# TankBoardSheet4.net
KiCad netlist of a schematic drawn in Altium Designer
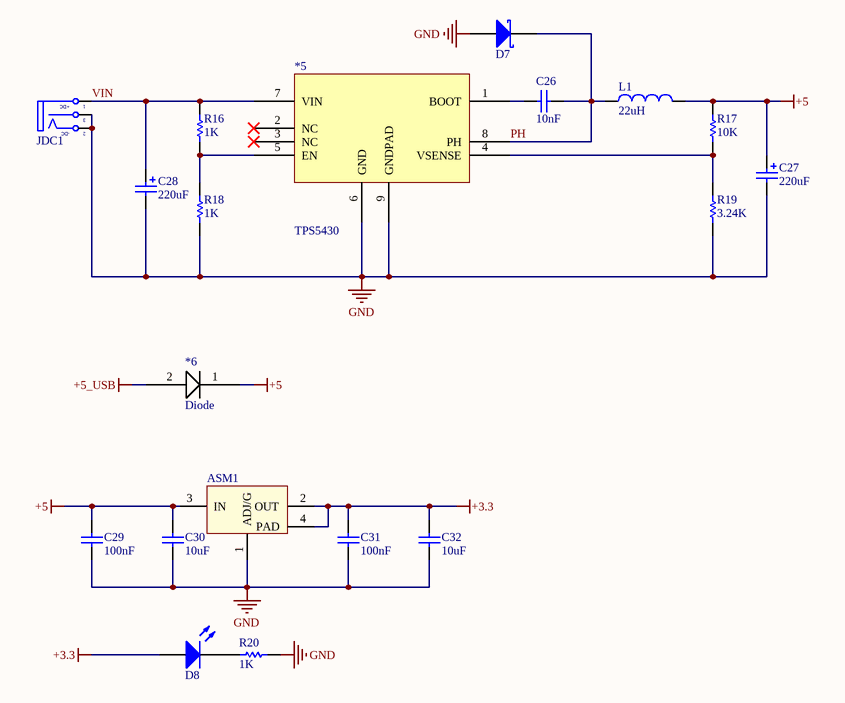
[diagram p0: TankBoardSheet4.SchDoc]

(export (version "E")
  (design (tool "Eeschema 10.0.6"))
  (components
    (comp (ref "*5")
      (value "TPS5430")
      (footprint "SOIC127P600X170_HS-9N")
      (libsource (lib "MiclsLib") (part "TPS5430"))
    )
    (comp (ref "*6")
      (value "Diode")
      (footprint "DIODE SMA (DO-214AC)")
      (libsource (lib "MiclsLib") (part "Diode"))
    )
    (comp (ref "ASM1")
      (value "LM1117")
      (footprint "SOT223-4N")
      (description "Available in 1.8V, 2.5V, 2.85V, 3.3V, 5V, and  Adjustable Versions")
      (libsource (lib "PIF_Library") (part "LM1117"))
    )
    (comp (ref "C26")
      (value "10nF")
      (footprint "CAP-SM-0603")
      (description "Capacitor")
      (fields (field (name "Comment") "Cap Non-Pol SMD"))
      (libsource (lib "PIF_Library") (part "Cap Non-Pol SMD"))
    )
    (comp (ref "C27")
      (value "220uF")
      (footprint "CAP ALU SIZE D")
      (description "Polarized Capacitor (Radial)")
      (fields (field (name "Comment") "Cap Pol SMD"))
      (libsource (lib "PIF_Library") (part "Cap Pol SMD"))
    )
    (comp (ref "C28")
      (value "220uF")
      (footprint "CAP ALU SIZE D")
      (description "Polarized Capacitor (Radial)")
      (fields (field (name "Comment") "Cap Pol SMD"))
      (libsource (lib "PIF_Library") (part "Cap Pol SMD"))
    )
    (comp (ref "C29")
      (value "100nF")
      (footprint "CAP-SM-0603")
      (description "Capacitor")
      (fields (field (name "Comment") "Cap Non-Pol SMD"))
      (libsource (lib "PIF_Library") (part "Cap Non-Pol SMD"))
    )
    (comp (ref "C30")
      (value "10uF")
      (footprint "CAP-SM-0603")
      (description "Capacitor")
      (fields (field (name "Comment") "Cap Non-Pol SMD"))
      (libsource (lib "PIF_Library") (part "Cap Non-Pol SMD"))
    )
    (comp (ref "C31")
      (value "100nF")
      (footprint "CAP-SM-0603")
      (description "Capacitor")
      (fields (field (name "Comment") "Cap Non-Pol SMD"))
      (libsource (lib "PIF_Library") (part "Cap Non-Pol SMD"))
    )
    (comp (ref "C32")
      (value "10uF")
      (footprint "CAP-SM-0603")
      (description "Capacitor")
      (fields (field (name "Comment") "Cap Non-Pol SMD"))
      (libsource (lib "PIF_Library") (part "Cap Non-Pol SMD"))
    )
    (comp (ref "D7")
      (value "D Schottky")
      (footprint "SS34")
      (description "Schottky Diode")
      (fields (field (name "PUBLISHER") "Altium Limited"))
      (libsource (lib "PIF_Library") (part "D Schottky"))
    )
    (comp (ref "D8")
      (value "LED SMD")
      (footprint "LED_0603_Blue")
      (description "LED")
      (libsource (lib "PIF_Library") (part "LED SMD"))
    )
    (comp (ref "JDC1")
      (value "Jack DC")
      (footprint "DC-IN")
      (description "Jack DC input")
      (libsource (lib "PIF_Library") (part "Jack DC"))
    )
    (comp (ref "L1")
      (value "22uH")
      (footprint "INDUCTOR 12.5x12.5")
      (description "Inductor")
      (libsource (lib "PIF_Library") (part "Inductor"))
    )
    (comp (ref "R16")
      (value "1K")
      (footprint "RES-SM-0603")
      (description "Resistor")
      (fields (field (name "Comment") "RESISTOR SMD"))
      (libsource (lib "PIF_Library") (part "RESISTOR SMD"))
    )
    (comp (ref "R17")
      (value "10K")
      (footprint "RES-SM-0603")
      (description "Resistor")
      (fields (field (name "Comment") "RESISTOR SMD"))
      (libsource (lib "PIF_Library") (part "RESISTOR SMD"))
    )
    (comp (ref "R18")
      (value "1K")
      (footprint "RES-SM-0603")
      (description "Resistor")
      (fields (field (name "Comment") "RESISTOR SMD"))
      (libsource (lib "PIF_Library") (part "RESISTOR SMD"))
    )
    (comp (ref "R19")
      (value "3.24K")
      (footprint "RES-SM-0603")
      (description "Resistor")
      (fields (field (name "Comment") "RESISTOR SMD"))
      (libsource (lib "PIF_Library") (part "RESISTOR SMD"))
    )
    (comp (ref "R20")
      (value "1K")
      (footprint "RES-SM-0603")
      (description "Resistor")
      (fields (field (name "Comment") "RESISTOR SMD"))
      (libsource (lib "PIF_Library") (part "RESISTOR SMD"))
    )
  )
  (nets
    (net (code "1") (name "+3.3") (class "Default")
      (node (ref "ASM1") (pin "2") (pinfunction "OUT_2") (pintype "passive"))
      (node (ref "ASM1") (pin "4") (pinfunction "PAD_4") (pintype "passive"))
      (node (ref "C31") (pin "1") (pinfunction "1_1") (pintype "passive"))
      (node (ref "C32") (pin "1") (pinfunction "1_1") (pintype "passive"))
      (node (ref "D8") (pin "1") (pinfunction "A_1") (pintype "passive"))
    )
    (net (code "2") (name "+5") (class "Default")
      (node (ref "*6") (pin "1") (pinfunction "3_1") (pintype "passive"))
      (node (ref "ASM1") (pin "3") (pinfunction "IN_3") (pintype "passive"))
      (node (ref "C27") (pin "1") (pinfunction "1_1") (pintype "passive"))
      (node (ref "C29") (pin "1") (pinfunction "1_1") (pintype "passive"))
      (node (ref "C30") (pin "1") (pinfunction "1_1") (pintype "passive"))
      (node (ref "L1") (pin "2") (pinfunction "2_2") (pintype "passive"))
      (node (ref "R17") (pin "2") (pinfunction "2_2") (pintype "passive"))
    )
    (net (code "3") (name "+5_USB") (class "Default")
      (node (ref "*6") (pin "2") (pinfunction "4_2") (pintype "passive"))
    )
    (net (code "4") (name "/PH") (class "Default")
      (node (ref "*5") (pin "8") (pinfunction "PH_8") (pintype "passive"))
      (node (ref "C26") (pin "1") (pinfunction "1_1") (pintype "passive"))
      (node (ref "D7") (pin "2") (pinfunction "K_2") (pintype "passive"))
      (node (ref "L1") (pin "1") (pinfunction "1_1") (pintype "passive"))
    )
    (net (code "5") (name "/VIN") (class "Default")
      (node (ref "*5") (pin "7") (pinfunction "VIN_7") (pintype "passive"))
      (node (ref "C28") (pin "1") (pinfunction "1_1") (pintype "passive"))
      (node (ref "JDC1") (pin "1") (pinfunction "T_1") (pintype "passive"))
      (node (ref "R16") (pin "2") (pinfunction "2_2") (pintype "passive"))
    )
    (net (code "6") (name "GND") (class "Default")
      (node (ref "*5") (pin "6") (pinfunction "GND_6") (pintype "passive"))
      (node (ref "*5") (pin "9") (pinfunction "GNDPAD_9") (pintype "passive"))
      (node (ref "ASM1") (pin "1") (pinfunction "ADJ/G_1") (pintype "passive"))
      (node (ref "C27") (pin "2") (pinfunction "2_2") (pintype "passive"))
      (node (ref "C28") (pin "2") (pinfunction "2_2") (pintype "passive"))
      (node (ref "C29") (pin "2") (pinfunction "2_2") (pintype "passive"))
      (node (ref "C30") (pin "2") (pinfunction "2_2") (pintype "passive"))
      (node (ref "C31") (pin "2") (pinfunction "2_2") (pintype "passive"))
      (node (ref "C32") (pin "2") (pinfunction "2_2") (pintype "passive"))
      (node (ref "D7") (pin "1") (pinfunction "A_1") (pintype "passive"))
      (node (ref "JDC1") (pin "2") (pinfunction "TN_2") (pintype "passive"))
      (node (ref "JDC1") (pin "3") (pinfunction "S_3") (pintype "power_in"))
      (node (ref "R18") (pin "1") (pinfunction "1_1") (pintype "passive"))
      (node (ref "R19") (pin "1") (pinfunction "1_1") (pintype "passive"))
      (node (ref "R20") (pin "1") (pinfunction "1_1") (pintype "passive"))
    )
    (net (code "7") (name "Net-(*5-BOOT)") (class "Default")
      (node (ref "*5") (pin "1") (pinfunction "BOOT_1") (pintype "passive"))
      (node (ref "C26") (pin "2") (pinfunction "2_2") (pintype "passive"))
    )
    (net (code "8") (name "Net-(*5-EN)") (class "Default")
      (node (ref "*5") (pin "5") (pinfunction "EN_5") (pintype "passive"))
      (node (ref "R16") (pin "1") (pinfunction "1_1") (pintype "passive"))
      (node (ref "R18") (pin "2") (pinfunction "2_2") (pintype "passive"))
    )
    (net (code "9") (name "Net-(*5-VSENSE)") (class "Default")
      (node (ref "*5") (pin "4") (pinfunction "VSENSE_4") (pintype "passive"))
      (node (ref "R17") (pin "1") (pinfunction "1_1") (pintype "passive"))
      (node (ref "R19") (pin "2") (pinfunction "2_2") (pintype "passive"))
    )
    (net (code "10") (name "Net-(D8-K)") (class "Default")
      (node (ref "D8") (pin "2") (pinfunction "K_2") (pintype "passive"))
      (node (ref "R20") (pin "2") (pinfunction "2_2") (pintype "passive"))
    )
    (net (code "11") (name "unconnected-(*5-NC-Pad2)") (class "Default")
      (node (ref "*5") (pin "2") (pinfunction "NC_2") (pintype "passive+no_connect"))
    )
    (net (code "12") (name "unconnected-(*5-NC-Pad3)") (class "Default")
      (node (ref "*5") (pin "3") (pinfunction "NC_3") (pintype "passive+no_connect"))
    )
  )
)
